# main.net
KiCad netlist of a schematic drawn in Altium Designer
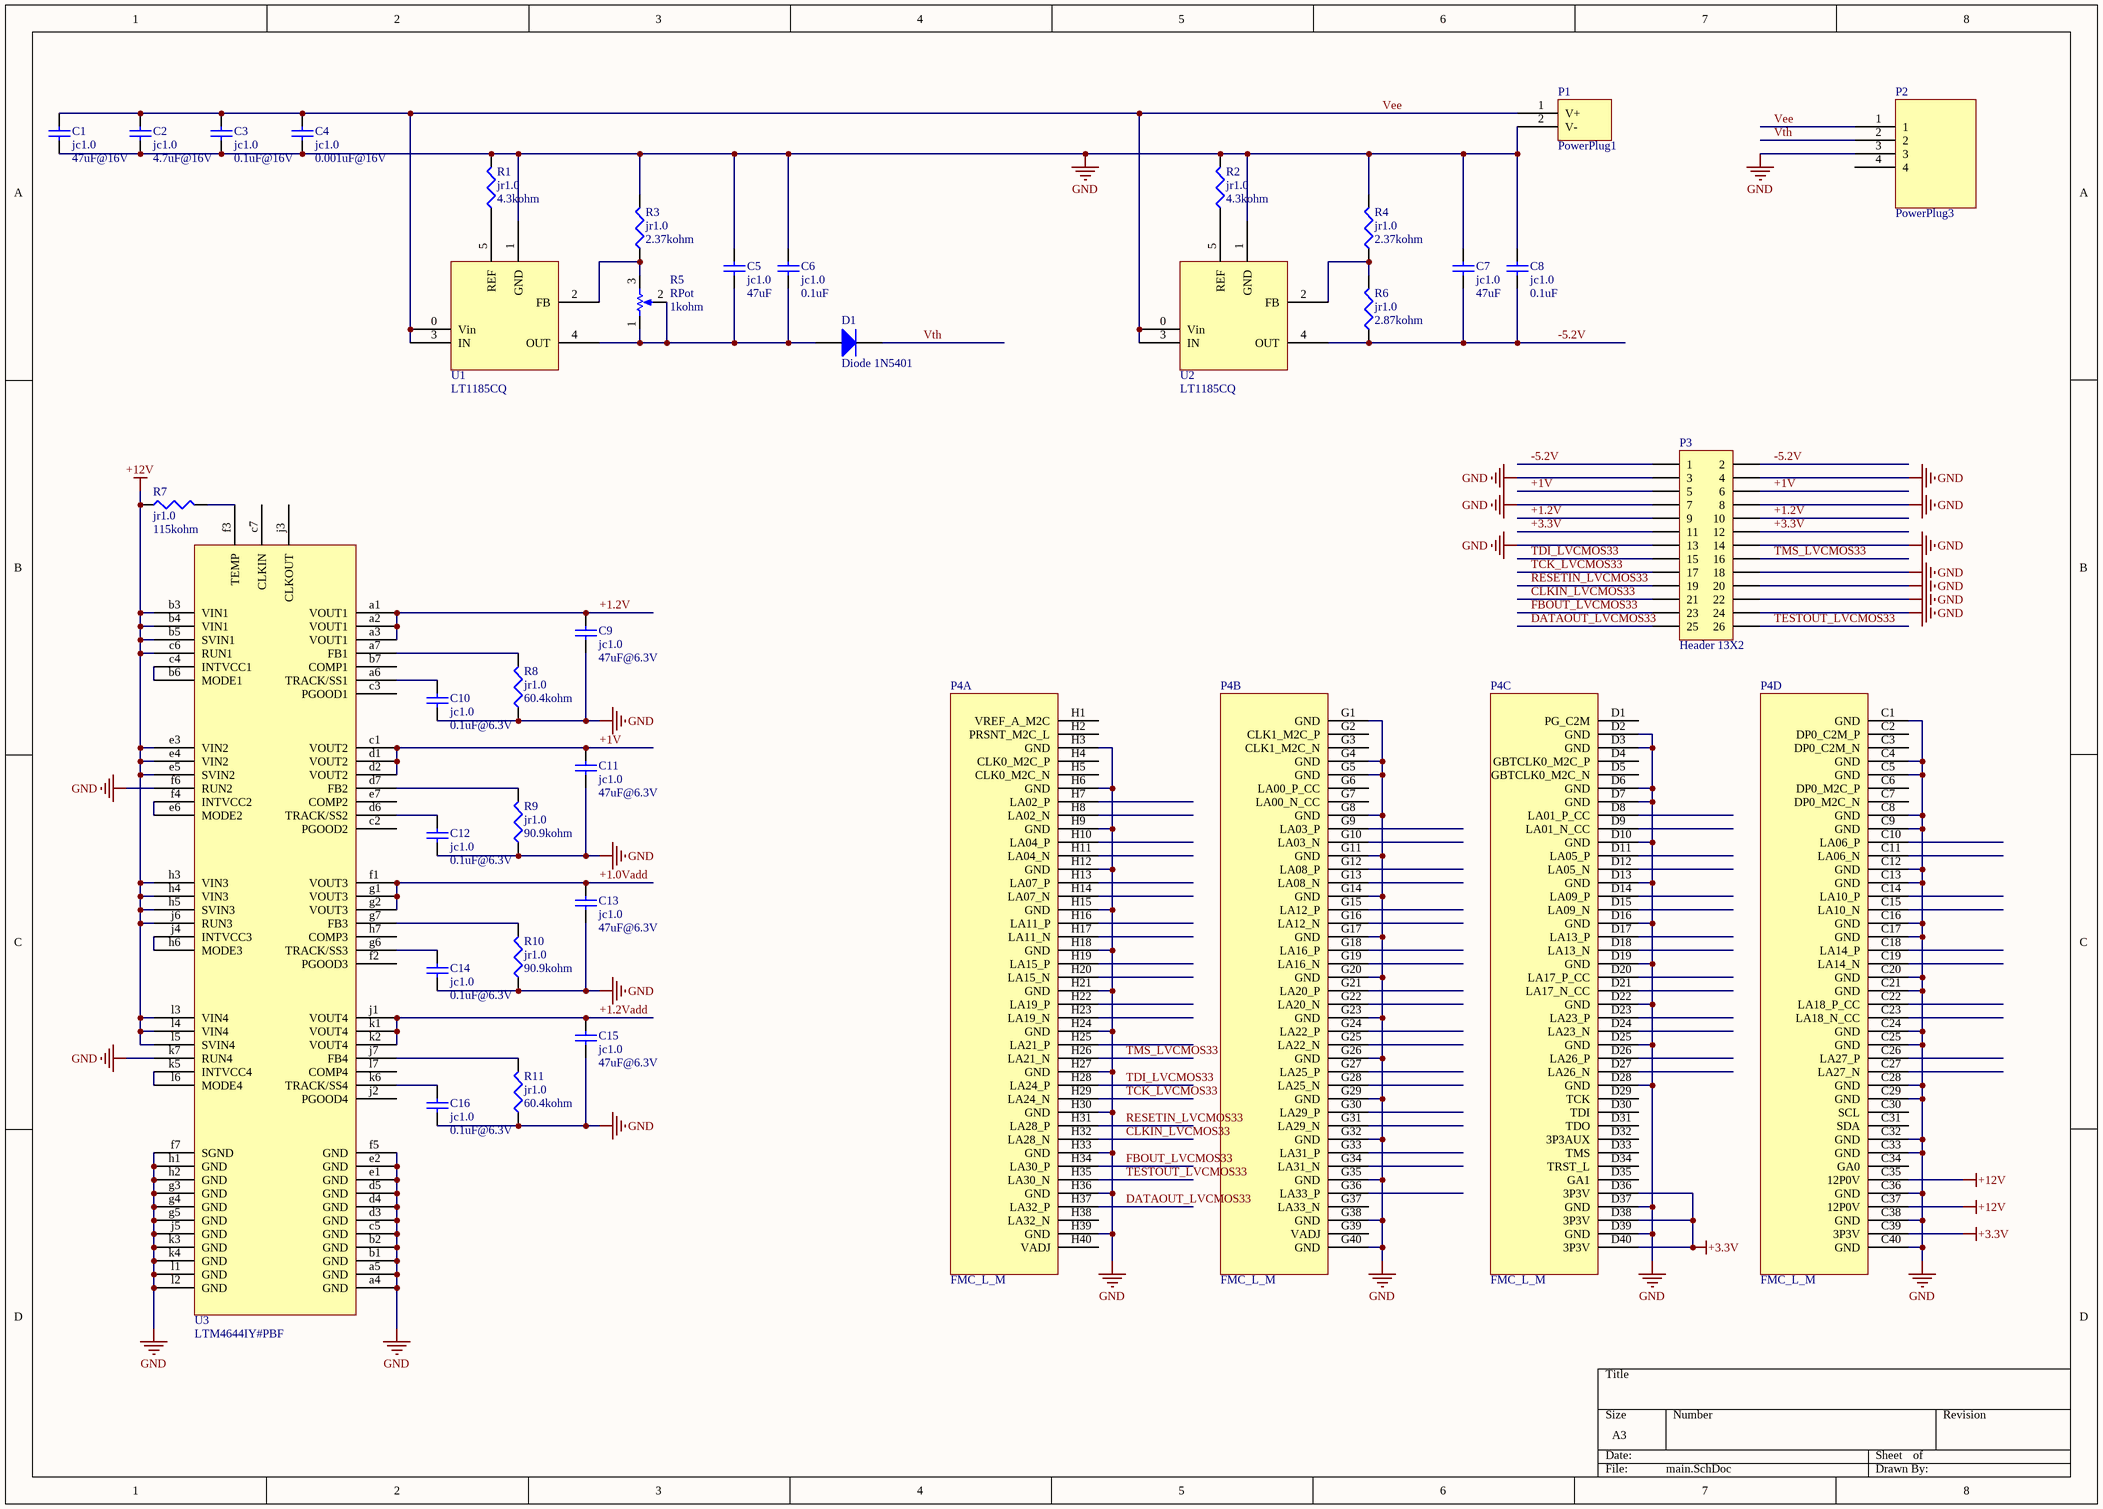
[diagram p0: main.SchDoc]

(export (version "E")
  (design (tool "Eeschema 10.0.6"))
  (components
    (comp (ref "C1")
      (value "jc1.0")
      (footprint "2220")
      (description "Capacitor")
      (fields (field (name "ALTIUM_VALUE") "47uF@16V") (field (name "PUBLISHER") "Altium Limited"))
      (libsource (lib "LIB01DXP2006SchLib") (part "Cap"))
    )
    (comp (ref "C2")
      (value "jc1.0")
      (footprint "2220")
      (description "Capacitor")
      (fields (field (name "ALTIUM_VALUE") "4.7uF@16V") (field (name "PUBLISHER") "Altium Limited"))
      (libsource (lib "LIB01DXP2006SchLib") (part "Cap"))
    )
    (comp (ref "C3")
      (value "jc1.0")
      (footprint "2220")
      (description "Capacitor")
      (fields (field (name "ALTIUM_VALUE") "0.1uF@16V") (field (name "PUBLISHER") "Altium Limited"))
      (libsource (lib "LIB01DXP2006SchLib") (part "Cap"))
    )
    (comp (ref "C4")
      (value "jc1.0")
      (footprint "2220")
      (description "Capacitor")
      (fields (field (name "ALTIUM_VALUE") "0.001uF@16V") (field (name "PUBLISHER") "Altium Limited"))
      (libsource (lib "LIB01DXP2006SchLib") (part "Cap"))
    )
    (comp (ref "C5")
      (value "jc1.0")
      (footprint "2220")
      (description "Capacitor")
      (fields (field (name "ALTIUM_VALUE") "47uF") (field (name "PUBLISHER") "Altium Limited"))
      (libsource (lib "LIB01DXP2006SchLib") (part "Cap"))
    )
    (comp (ref "C6")
      (value "jc1.0")
      (footprint "2220")
      (description "Capacitor")
      (fields (field (name "ALTIUM_VALUE") "0.1uF") (field (name "PUBLISHER") "Altium Limited"))
      (libsource (lib "LIB01DXP2006SchLib") (part "Cap"))
    )
    (comp (ref "C7")
      (value "jc1.0")
      (footprint "2220")
      (description "Capacitor")
      (fields (field (name "ALTIUM_VALUE") "47uF") (field (name "PUBLISHER") "Altium Limited"))
      (libsource (lib "LIB01DXP2006SchLib") (part "Cap"))
    )
    (comp (ref "C8")
      (value "jc1.0")
      (footprint "2220")
      (description "Capacitor")
      (fields (field (name "ALTIUM_VALUE") "0.1uF") (field (name "PUBLISHER") "Altium Limited"))
      (libsource (lib "LIB01DXP2006SchLib") (part "Cap"))
    )
    (comp (ref "C9")
      (value "jc1.0")
      (footprint "0805")
      (description "Capacitor")
      (fields (field (name "ALTIUM_VALUE") "47uF@6.3V") (field (name "PUBLISHER") "Altium Limited"))
      (libsource (lib "LIB01DXP2006SchLib") (part "Cap"))
    )
    (comp (ref "C10")
      (value "jc1.0")
      (footprint "0402")
      (description "Capacitor")
      (fields (field (name "ALTIUM_VALUE") "0.1uF@6.3V") (field (name "PUBLISHER") "Altium Limited"))
      (libsource (lib "LIB01DXP2006SchLib") (part "Cap"))
    )
    (comp (ref "C11")
      (value "jc1.0")
      (footprint "0805")
      (description "Capacitor")
      (fields (field (name "ALTIUM_VALUE") "47uF@6.3V") (field (name "PUBLISHER") "Altium Limited"))
      (libsource (lib "LIB01DXP2006SchLib") (part "Cap"))
    )
    (comp (ref "C12")
      (value "jc1.0")
      (footprint "0402")
      (description "Capacitor")
      (fields (field (name "ALTIUM_VALUE") "0.1uF@6.3V") (field (name "PUBLISHER") "Altium Limited"))
      (libsource (lib "LIB01DXP2006SchLib") (part "Cap"))
    )
    (comp (ref "C13")
      (value "jc1.0")
      (footprint "0805")
      (description "Capacitor")
      (fields (field (name "ALTIUM_VALUE") "47uF@6.3V") (field (name "PUBLISHER") "Altium Limited"))
      (libsource (lib "LIB01DXP2006SchLib") (part "Cap"))
    )
    (comp (ref "C14")
      (value "jc1.0")
      (footprint "0402")
      (description "Capacitor")
      (fields (field (name "ALTIUM_VALUE") "0.1uF@6.3V") (field (name "PUBLISHER") "Altium Limited"))
      (libsource (lib "LIB01DXP2006SchLib") (part "Cap"))
    )
    (comp (ref "C15")
      (value "jc1.0")
      (footprint "0805")
      (description "Capacitor")
      (fields (field (name "ALTIUM_VALUE") "47uF@6.3V") (field (name "PUBLISHER") "Altium Limited"))
      (libsource (lib "LIB01DXP2006SchLib") (part "Cap"))
    )
    (comp (ref "C16")
      (value "jc1.0")
      (footprint "0402")
      (description "Capacitor")
      (fields (field (name "ALTIUM_VALUE") "0.1uF@6.3V") (field (name "PUBLISHER") "Altium Limited"))
      (libsource (lib "LIB01DXP2006SchLib") (part "Cap"))
    )
    (comp (ref "D1")
      (value "Diode 1N5401")
      (footprint "DO-201AD")
      (description "3 Amp General Purpose Rectifier")
      (fields (field (name "PUBLISHER") "Altium Limited"))
      (libsource (lib "Miscellaneous Devices") (part "Diode 1N5401"))
    )
    (comp (ref "P1")
      (value "PowerPlug1")
      (footprint "POWERPLUG1")
      (libsource (lib "LIB01DXP2006SchLib") (part "PowerPlug1"))
    )
    (comp (ref "P2")
      (value "PowerPlug3")
      (footprint "POWERPLUG3")
      (libsource (lib "LIB01DXP2006SchLib") (part "PowerPlug3"))
    )
    (comp (ref "P3")
      (value "Header 13X2")
      (footprint "HDR2X13")
      (description "Header, 13-Pin, Dual row")
      (fields (field (name "PUBLISHER") "Altium Limited"))
      (libsource (lib "Miscellaneous Connectors") (part "Header 13X2"))
    )
    (comp (ref "P4")
      (value "FMC_L_M")
      (footprint "ASP-134606-01")
      (libsource (lib "LIB01DXP2006SchLib") (part "FMC_L_M"))
    )
    (comp (ref "R1")
      (value "jr1.0")
      (footprint "0805")
      (description "Resistor")
      (fields (field (name "ALTIUM_VALUE") "4.3kohm") (field (name "PUBLISHER") "Altium Limited"))
      (libsource (lib "LIB01DXP2006SchLib") (part "Res"))
    )
    (comp (ref "R2")
      (value "jr1.0")
      (footprint "0805")
      (description "Resistor")
      (fields (field (name "ALTIUM_VALUE") "4.3kohm") (field (name "PUBLISHER") "Altium Limited"))
      (libsource (lib "LIB01DXP2006SchLib") (part "Res"))
    )
    (comp (ref "R3")
      (value "jr1.0")
      (footprint "0805")
      (description "Resistor")
      (fields (field (name "ALTIUM_VALUE") "2.37kohm") (field (name "PUBLISHER") "Altium Limited"))
      (libsource (lib "LIB01DXP2006SchLib") (part "Res"))
    )
    (comp (ref "R4")
      (value "jr1.0")
      (footprint "0805")
      (description "Resistor")
      (fields (field (name "ALTIUM_VALUE") "2.37kohm") (field (name "PUBLISHER") "Altium Limited"))
      (libsource (lib "LIB01DXP2006SchLib") (part "Res"))
    )
    (comp (ref "R5")
      (value "RPot")
      (footprint "VR5")
      (description "Potentiometer")
      (fields (field (name "ALTIUM_VALUE") "1kohm") (field (name "PUBLISHER") "Altium Limited"))
      (libsource (lib "LIB01DXP2006SchLib") (part "RPot"))
    )
    (comp (ref "R6")
      (value "jr1.0")
      (footprint "0805")
      (description "Resistor")
      (fields (field (name "ALTIUM_VALUE") "2.87kohm") (field (name "PUBLISHER") "Altium Limited"))
      (libsource (lib "LIB01DXP2006SchLib") (part "Res"))
    )
    (comp (ref "R7")
      (value "jr1.0")
      (footprint "0402")
      (description "Resistor")
      (fields (field (name "ALTIUM_VALUE") "115kohm") (field (name "PUBLISHER") "Altium Limited"))
      (libsource (lib "LIB01DXP2006SchLib") (part "Res"))
    )
    (comp (ref "R8")
      (value "jr1.0")
      (footprint "0805")
      (description "Resistor")
      (fields (field (name "ALTIUM_VALUE") "60.4kohm") (field (name "PUBLISHER") "Altium Limited"))
      (libsource (lib "LIB01DXP2006SchLib") (part "Res"))
    )
    (comp (ref "R9")
      (value "jr1.0")
      (footprint "0805")
      (description "Resistor")
      (fields (field (name "ALTIUM_VALUE") "90.9kohm") (field (name "PUBLISHER") "Altium Limited"))
      (libsource (lib "LIB01DXP2006SchLib") (part "Res"))
    )
    (comp (ref "R10")
      (value "jr1.0")
      (footprint "0805")
      (description "Resistor")
      (fields (field (name "ALTIUM_VALUE") "90.9kohm") (field (name "PUBLISHER") "Altium Limited"))
      (libsource (lib "LIB01DXP2006SchLib") (part "Res"))
    )
    (comp (ref "R11")
      (value "jr1.0")
      (footprint "0805")
      (description "Resistor")
      (fields (field (name "ALTIUM_VALUE") "60.4kohm") (field (name "PUBLISHER") "Altium Limited"))
      (libsource (lib "LIB01DXP2006SchLib") (part "Res"))
    )
    (comp (ref "U1")
      (value "LT1185CQ")
      (footprint "LP5 - 1185")
      (libsource (lib "LIB01DXP2006SchLib") (part "LT1185CQ"))
    )
    (comp (ref "U2")
      (value "LT1185CQ")
      (footprint "LP5 - 1185")
      (libsource (lib "LIB01DXP2006SchLib") (part "LT1185CQ"))
    )
    (comp (ref "U3")
      (value "LTM4644IY#PBF")
      (footprint "BGA77C127P7X11_900X1500X521")
      (libsource (lib "LIB01DXP2006SchLib") (part "LTM4644IY#PBF"))
    )
  )
  (nets
    (net (code "1") (name "+3.3V") (class "Default")
      (node (ref "P3") (pin "11") (pinfunction "11_11") (pintype "passive"))
      (node (ref "P3") (pin "12") (pinfunction "12_12") (pintype "passive"))
      (node (ref "P4") (pin "C39") (pinfunction "3P3V_C39") (pintype "passive"))
      (node (ref "P4") (pin "D36") (pinfunction "3P3V_D36") (pintype "passive"))
      (node (ref "P4") (pin "D38") (pinfunction "3P3V_D38") (pintype "passive"))
      (node (ref "P4") (pin "D40") (pinfunction "3P3V_D40") (pintype "passive"))
    )
    (net (code "2") (name "+12V") (class "Default")
      (node (ref "P4") (pin "C35") (pinfunction "12P0V_C35") (pintype "passive"))
      (node (ref "P4") (pin "C37") (pinfunction "12P0V_C37") (pintype "passive"))
      (node (ref "R7") (pin "1") (pinfunction "1_1") (pintype "passive"))
      (node (ref "U3") (pin "b3") (pinfunction "VIN1_b3") (pintype "passive"))
      (node (ref "U3") (pin "b4") (pinfunction "VIN1_b4") (pintype "passive"))
      (node (ref "U3") (pin "b5") (pinfunction "SVIN1_b5") (pintype "passive"))
      (node (ref "U3") (pin "c6") (pinfunction "RUN1_c6") (pintype "passive"))
      (node (ref "U3") (pin "e3") (pinfunction "VIN2_e3") (pintype "passive"))
      (node (ref "U3") (pin "e4") (pinfunction "VIN2_e4") (pintype "passive"))
      (node (ref "U3") (pin "e5") (pinfunction "SVIN2_e5") (pintype "passive"))
      (node (ref "U3") (pin "h3") (pinfunction "VIN3_h3") (pintype "passive"))
      (node (ref "U3") (pin "h4") (pinfunction "VIN3_h4") (pintype "passive"))
      (node (ref "U3") (pin "h5") (pinfunction "SVIN3_h5") (pintype "passive"))
      (node (ref "U3") (pin "j6") (pinfunction "RUN3_j6") (pintype "passive"))
      (node (ref "U3") (pin "l3") (pinfunction "VIN4_l3") (pintype "passive"))
      (node (ref "U3") (pin "l4") (pinfunction "VIN4_l4") (pintype "passive"))
      (node (ref "U3") (pin "l5") (pinfunction "SVIN4_l5") (pintype "passive"))
    )
    (net (code "3") (name "/+1.0Vadd") (class "Default")
      (node (ref "C13") (pin "2") (pinfunction "2_2") (pintype "passive"))
      (node (ref "U3") (pin "f1") (pinfunction "VOUT3_f1") (pintype "passive"))
      (node (ref "U3") (pin "g1") (pinfunction "VOUT3_g1") (pintype "passive"))
      (node (ref "U3") (pin "g2") (pinfunction "VOUT3_g2") (pintype "passive"))
    )
    (net (code "4") (name "/+1.2V") (class "Default")
      (node (ref "C9") (pin "2") (pinfunction "2_2") (pintype "passive"))
      (node (ref "P3") (pin "10") (pinfunction "10_10") (pintype "passive"))
      (node (ref "P3") (pin "9") (pinfunction "9_9") (pintype "passive"))
      (node (ref "U3") (pin "a1") (pinfunction "VOUT1_a1") (pintype "passive"))
      (node (ref "U3") (pin "a2") (pinfunction "VOUT1_a2") (pintype "passive"))
      (node (ref "U3") (pin "a3") (pinfunction "VOUT1_a3") (pintype "passive"))
    )
    (net (code "5") (name "/+1.2Vadd") (class "Default")
      (node (ref "C15") (pin "2") (pinfunction "2_2") (pintype "passive"))
      (node (ref "U3") (pin "j1") (pinfunction "VOUT4_j1") (pintype "passive"))
      (node (ref "U3") (pin "k1") (pinfunction "VOUT4_k1") (pintype "passive"))
      (node (ref "U3") (pin "k2") (pinfunction "VOUT4_k2") (pintype "passive"))
    )
    (net (code "6") (name "/+1V") (class "Default")
      (node (ref "C11") (pin "2") (pinfunction "2_2") (pintype "passive"))
      (node (ref "P3") (pin "5") (pinfunction "5_5") (pintype "passive"))
      (node (ref "P3") (pin "6") (pinfunction "6_6") (pintype "passive"))
      (node (ref "U3") (pin "c1") (pinfunction "VOUT2_c1") (pintype "passive"))
      (node (ref "U3") (pin "d1") (pinfunction "VOUT2_d1") (pintype "passive"))
      (node (ref "U3") (pin "d2") (pinfunction "VOUT2_d2") (pintype "passive"))
    )
    (net (code "7") (name "/-5.2V") (class "Default")
      (node (ref "C7") (pin "1") (pinfunction "1_1") (pintype "passive"))
      (node (ref "C8") (pin "1") (pinfunction "1_1") (pintype "passive"))
      (node (ref "P3") (pin "1") (pinfunction "1_1") (pintype "passive"))
      (node (ref "P3") (pin "2") (pinfunction "2_2") (pintype "passive"))
      (node (ref "R6") (pin "1") (pinfunction "1_1") (pintype "passive"))
      (node (ref "U2") (pin "4") (pinfunction "OUT_4") (pintype "passive"))
    )
    (net (code "8") (name "/CLKIN_LVCMOS33") (class "Default")
      (node (ref "P3") (pin "21") (pinfunction "21_21") (pintype "passive"))
      (node (ref "P4") (pin "H32") (pinfunction "LA28_N_H32") (pintype "passive"))
    )
    (net (code "9") (name "/DATAOUT_LVCMOS33") (class "Default")
      (node (ref "P3") (pin "25") (pinfunction "25_25") (pintype "passive"))
      (node (ref "P4") (pin "H37") (pinfunction "LA32_P_H37") (pintype "passive"))
    )
    (net (code "10") (name "/FBOUT_LVCMOS33") (class "Default")
      (node (ref "P3") (pin "23") (pinfunction "23_23") (pintype "passive"))
      (node (ref "P4") (pin "H34") (pinfunction "LA30_P_H34") (pintype "passive"))
    )
    (net (code "11") (name "/RESETIN_LVCMOS33") (class "Default")
      (node (ref "P3") (pin "19") (pinfunction "19_19") (pintype "passive"))
      (node (ref "P4") (pin "H31") (pinfunction "LA28_P_H31") (pintype "passive"))
    )
    (net (code "12") (name "/TCK_LVCMOS33") (class "Default")
      (node (ref "P3") (pin "17") (pinfunction "17_17") (pintype "passive"))
      (node (ref "P4") (pin "H29") (pinfunction "LA24_N_H29") (pintype "passive"))
    )
    (net (code "13") (name "/TDI_LVCMOS33") (class "Default")
      (node (ref "P3") (pin "15") (pinfunction "15_15") (pintype "passive"))
      (node (ref "P4") (pin "H28") (pinfunction "LA24_P_H28") (pintype "passive"))
    )
    (net (code "14") (name "/TESTOUT_LVCMOS33") (class "Default")
      (node (ref "P3") (pin "26") (pinfunction "26_26") (pintype "passive"))
      (node (ref "P4") (pin "H35") (pinfunction "LA30_N_H35") (pintype "passive"))
    )
    (net (code "15") (name "/TMS_LVCMOS33") (class "Default")
      (node (ref "P3") (pin "16") (pinfunction "16_16") (pintype "passive"))
      (node (ref "P4") (pin "H26") (pinfunction "LA21_N_H26") (pintype "passive"))
    )
    (net (code "16") (name "/Vee") (class "Default")
      (node (ref "C1") (pin "2") (pinfunction "2_2") (pintype "passive"))
      (node (ref "C2") (pin "2") (pinfunction "2_2") (pintype "passive"))
      (node (ref "C3") (pin "2") (pinfunction "2_2") (pintype "passive"))
      (node (ref "C4") (pin "2") (pinfunction "2_2") (pintype "passive"))
      (node (ref "P1") (pin "1") (pinfunction "V+_1") (pintype "passive"))
      (node (ref "P2") (pin "1") (pinfunction "1_1") (pintype "passive"))
      (node (ref "U1") (pin "0") (pinfunction "Vin_0") (pintype "passive"))
      (node (ref "U1") (pin "3") (pinfunction "IN_3") (pintype "passive"))
      (node (ref "U2") (pin "0") (pinfunction "Vin_0") (pintype "passive"))
      (node (ref "U2") (pin "3") (pinfunction "IN_3") (pintype "passive"))
    )
    (net (code "17") (name "/Vth") (class "Default")
      (node (ref "D1") (pin "2") (pinfunction "K_2") (pintype "passive"))
      (node (ref "P2") (pin "2") (pinfunction "2_2") (pintype "passive"))
    )
    (net (code "18") (name "GND") (class "Default")
      (node (ref "C1") (pin "1") (pinfunction "1_1") (pintype "passive"))
      (node (ref "C10") (pin "1") (pinfunction "1_1") (pintype "passive"))
      (node (ref "C11") (pin "1") (pinfunction "1_1") (pintype "passive"))
      (node (ref "C12") (pin "1") (pinfunction "1_1") (pintype "passive"))
      (node (ref "C13") (pin "1") (pinfunction "1_1") (pintype "passive"))
      (node (ref "C14") (pin "1") (pinfunction "1_1") (pintype "passive"))
      (node (ref "C15") (pin "1") (pinfunction "1_1") (pintype "passive"))
      (node (ref "C16") (pin "1") (pinfunction "1_1") (pintype "passive"))
      (node (ref "C2") (pin "1") (pinfunction "1_1") (pintype "passive"))
      (node (ref "C3") (pin "1") (pinfunction "1_1") (pintype "passive"))
      (node (ref "C4") (pin "1") (pinfunction "1_1") (pintype "passive"))
      (node (ref "C5") (pin "2") (pinfunction "2_2") (pintype "passive"))
      (node (ref "C6") (pin "2") (pinfunction "2_2") (pintype "passive"))
      (node (ref "C7") (pin "2") (pinfunction "2_2") (pintype "passive"))
      (node (ref "C8") (pin "2") (pinfunction "2_2") (pintype "passive"))
      (node (ref "C9") (pin "1") (pinfunction "1_1") (pintype "passive"))
      (node (ref "P1") (pin "2") (pinfunction "V-_2") (pintype "passive"))
      (node (ref "P2") (pin "3") (pinfunction "3_3") (pintype "passive"))
      (node (ref "P3") (pin "13") (pinfunction "13_13") (pintype "passive"))
      (node (ref "P3") (pin "14") (pinfunction "14_14") (pintype "passive"))
      (node (ref "P3") (pin "18") (pinfunction "18_18") (pintype "passive"))
      (node (ref "P3") (pin "20") (pinfunction "20_20") (pintype "passive"))
      (node (ref "P3") (pin "22") (pinfunction "22_22") (pintype "passive"))
      (node (ref "P3") (pin "24") (pinfunction "24_24") (pintype "passive"))
      (node (ref "P3") (pin "3") (pinfunction "3_3") (pintype "passive"))
      (node (ref "P3") (pin "4") (pinfunction "4_4") (pintype "passive"))
      (node (ref "P3") (pin "7") (pinfunction "7_7") (pintype "passive"))
      (node (ref "P3") (pin "8") (pinfunction "8_8") (pintype "passive"))
      (node (ref "P4") (pin "C1") (pinfunction "GND_C1") (pintype "passive"))
      (node (ref "P4") (pin "C12") (pinfunction "GND_C12") (pintype "passive"))
      (node (ref "P4") (pin "C13") (pinfunction "GND_C13") (pintype "passive"))
      (node (ref "P4") (pin "C16") (pinfunction "GND_C16") (pintype "passive"))
      (node (ref "P4") (pin "C17") (pinfunction "GND_C17") (pintype "passive"))
      (node (ref "P4") (pin "C20") (pinfunction "GND_C20") (pintype "passive"))
      (node (ref "P4") (pin "C21") (pinfunction "GND_C21") (pintype "passive"))
      (node (ref "P4") (pin "C24") (pinfunction "GND_C24") (pintype "passive"))
      (node (ref "P4") (pin "C25") (pinfunction "GND_C25") (pintype "passive"))
      (node (ref "P4") (pin "C28") (pinfunction "GND_C28") (pintype "passive"))
      (node (ref "P4") (pin "C29") (pinfunction "GND_C29") (pintype "passive"))
      (node (ref "P4") (pin "C32") (pinfunction "GND_C32") (pintype "passive"))
      (node (ref "P4") (pin "C33") (pinfunction "GND_C33") (pintype "passive"))
      (node (ref "P4") (pin "C36") (pinfunction "GND_C36") (pintype "passive"))
      (node (ref "P4") (pin "C38") (pinfunction "GND_C38") (pintype "passive"))
      (node (ref "P4") (pin "C4") (pinfunction "GND_C4") (pintype "passive"))
      (node (ref "P4") (pin "C40") (pinfunction "GND_C40") (pintype "passive"))
      (node (ref "P4") (pin "C5") (pinfunction "GND_C5") (pintype "passive"))
      (node (ref "P4") (pin "C8") (pinfunction "GND_C8") (pintype "passive"))
      (node (ref "P4") (pin "C9") (pinfunction "GND_C9") (pintype "passive"))
      (node (ref "P4") (pin "D10") (pinfunction "GND_D10") (pintype "passive"))
      (node (ref "P4") (pin "D13") (pinfunction "GND_D13") (pintype "passive"))
      (node (ref "P4") (pin "D16") (pinfunction "GND_D16") (pintype "passive"))
      (node (ref "P4") (pin "D19") (pinfunction "GND_D19") (pintype "passive"))
      (node (ref "P4") (pin "D2") (pinfunction "GND_D2") (pintype "passive"))
      (node (ref "P4") (pin "D22") (pinfunction "GND_D22") (pintype "passive"))
      (node (ref "P4") (pin "D25") (pinfunction "GND_D25") (pintype "passive"))
      (node (ref "P4") (pin "D28") (pinfunction "GND_D28") (pintype "passive"))
      (node (ref "P4") (pin "D3") (pinfunction "GND_D3") (pintype "passive"))
      (node (ref "P4") (pin "D37") (pinfunction "GND_D37") (pintype "passive"))
      (node (ref "P4") (pin "D39") (pinfunction "GND_D39") (pintype "passive"))
      (node (ref "P4") (pin "D6") (pinfunction "GND_D6") (pintype "passive"))
      (node (ref "P4") (pin "D7") (pinfunction "GND_D7") (pintype "passive"))
      (node (ref "P4") (pin "G1") (pinfunction "GND_G1") (pintype "passive"))
      (node (ref "P4") (pin "G11") (pinfunction "GND_G11") (pintype "passive"))
      (node (ref "P4") (pin "G14") (pinfunction "GND_G14") (pintype "passive"))
      (node (ref "P4") (pin "G17") (pinfunction "GND_G17") (pintype "passive"))
      (node (ref "P4") (pin "G20") (pinfunction "GND_G20") (pintype "passive"))
      (node (ref "P4") (pin "G23") (pinfunction "GND_G23") (pintype "passive"))
      (node (ref "P4") (pin "G26") (pinfunction "GND_G26") (pintype "passive"))
      (node (ref "P4") (pin "G29") (pinfunction "GND_G29") (pintype "passive"))
      (node (ref "P4") (pin "G32") (pinfunction "GND_G32") (pintype "passive"))
      (node (ref "P4") (pin "G35") (pinfunction "GND_G35") (pintype "passive"))
      (node (ref "P4") (pin "G38") (pinfunction "GND_G38") (pintype "passive"))
      (node (ref "P4") (pin "G4") (pinfunction "GND_G4") (pintype "passive"))
      (node (ref "P4") (pin "G40") (pinfunction "GND_G40") (pintype "passive"))
      (node (ref "P4") (pin "G5") (pinfunction "GND_G5") (pintype "passive"))
      (node (ref "P4") (pin "G8") (pinfunction "GND_G8") (pintype "passive"))
      (node (ref "P4") (pin "H12") (pinfunction "GND_H12") (pintype "passive"))
      (node (ref "P4") (pin "H15") (pinfunction "GND_H15") (pintype "passive"))
      (node (ref "P4") (pin "H18") (pinfunction "GND_H18") (pintype "passive"))
      (node (ref "P4") (pin "H21") (pinfunction "GND_H21") (pintype "passive"))
      (node (ref "P4") (pin "H24") (pinfunction "GND_H24") (pintype "passive"))
      (node (ref "P4") (pin "H27") (pinfunction "GND_H27") (pintype "passive"))
      (node (ref "P4") (pin "H3") (pinfunction "GND_H3") (pintype "passive"))
      (node (ref "P4") (pin "H30") (pinfunction "GND_H30") (pintype "passive"))
      (node (ref "P4") (pin "H33") (pinfunction "GND_H33") (pintype "passive"))
      (node (ref "P4") (pin "H36") (pinfunction "GND_H36") (pintype "passive"))
      (node (ref "P4") (pin "H39") (pinfunction "GND_H39") (pintype "passive"))
      (node (ref "P4") (pin "H6") (pinfunction "GND_H6") (pintype "passive"))
      (node (ref "P4") (pin "H9") (pinfunction "GND_H9") (pintype "passive"))
      (node (ref "R1") (pin "2") (pinfunction "2_2") (pintype "passive"))
      (node (ref "R10") (pin "1") (pinfunction "1_1") (pintype "passive"))
      (node (ref "R11") (pin "1") (pinfunction "1_1") (pintype "passive"))
      (node (ref "R2") (pin "2") (pinfunction "2_2") (pintype "passive"))
      (node (ref "R3") (pin "2") (pinfunction "2_2") (pintype "passive"))
      (node (ref "R4") (pin "2") (pinfunction "2_2") (pintype "passive"))
      (node (ref "R8") (pin "1") (pinfunction "1_1") (pintype "passive"))
      (node (ref "R9") (pin "1") (pinfunction "1_1") (pintype "passive"))
      (node (ref "U1") (pin "1") (pinfunction "GND_1") (pintype "passive"))
      (node (ref "U2") (pin "1") (pinfunction "GND_1") (pintype "passive"))
      (node (ref "U3") (pin "a4") (pinfunction "GND_a4") (pintype "passive"))
      (node (ref "U3") (pin "a5") (pinfunction "GND_a5") (pintype "passive"))
      (node (ref "U3") (pin "b1") (pinfunction "GND_b1") (pintype "passive"))
      (node (ref "U3") (pin "b2") (pinfunction "GND_b2") (pintype "passive"))
      (node (ref "U3") (pin "c5") (pinfunction "GND_c5") (pintype "passive"))
      (node (ref "U3") (pin "d3") (pinfunction "GND_d3") (pintype "passive"))
      (node (ref "U3") (pin "d4") (pinfunction "GND_d4") (pintype "passive"))
      (node (ref "U3") (pin "d5") (pinfunction "GND_d5") (pintype "passive"))
      (node (ref "U3") (pin "e1") (pinfunction "GND_e1") (pintype "passive"))
      (node (ref "U3") (pin "e2") (pinfunction "GND_e2") (pintype "passive"))
      (node (ref "U3") (pin "f5") (pinfunction "GND_f5") (pintype "passive"))
      (node (ref "U3") (pin "f6") (pinfunction "RUN2_f6") (pintype "passive"))
      (node (ref "U3") (pin "f7") (pinfunction "SGND_f7") (pintype "passive"))
      (node (ref "U3") (pin "g3") (pinfunction "GND_g3") (pintype "passive"))
      (node (ref "U3") (pin "g4") (pinfunction "GND_g4") (pintype "passive"))
      (node (ref "U3") (pin "g5") (pinfunction "GND_g5") (pintype "passive"))
      (node (ref "U3") (pin "h1") (pinfunction "GND_h1") (pintype "passive"))
      (node (ref "U3") (pin "h2") (pinfunction "GND_h2") (pintype "passive"))
      (node (ref "U3") (pin "j5") (pinfunction "GND_j5") (pintype "passive"))
      (node (ref "U3") (pin "k3") (pinfunction "GND_k3") (pintype "passive"))
      (node (ref "U3") (pin "k4") (pinfunction "GND_k4") (pintype "passive"))
      (node (ref "U3") (pin "k7") (pinfunction "RUN4_k7") (pintype "passive"))
      (node (ref "U3") (pin "l1") (pinfunction "GND_l1") (pintype "passive"))
      (node (ref "U3") (pin "l2") (pinfunction "GND_l2") (pintype "passive"))
    )
    (net (code "19") (name "Net-(D1-A)") (class "Default")
      (node (ref "C5") (pin "1") (pinfunction "1_1") (pintype "passive"))
      (node (ref "C6") (pin "1") (pinfunction "1_1") (pintype "passive"))
      (node (ref "D1") (pin "1") (pinfunction "A_1") (pintype "passive"))
      (node (ref "R5") (pin "1") (pinfunction "TOP_1") (pintype "passive"))
      (node (ref "R5") (pin "2") (pinfunction "TAP_2") (pintype "passive"))
      (node (ref "U1") (pin "4") (pinfunction "OUT_4") (pintype "passive"))
    )
    (net (code "20") (name "Net-(R5-BOT)") (class "Default")
      (node (ref "R3") (pin "1") (pinfunction "1_1") (pintype "passive"))
      (node (ref "R5") (pin "3") (pinfunction "BOT_3") (pintype "passive"))
      (node (ref "U1") (pin "2") (pinfunction "FB_2") (pintype "passive"))
    )
    (net (code "21") (name "Net-(U1-REF)") (class "Default")
      (node (ref "R1") (pin "1") (pinfunction "1_1") (pintype "passive"))
      (node (ref "U1") (pin "5") (pinfunction "REF_5") (pintype "passive"))
    )
    (net (code "22") (name "Net-(U2-FB)") (class "Default")
      (node (ref "R4") (pin "1") (pinfunction "1_1") (pintype "passive"))
      (node (ref "R6") (pin "2") (pinfunction "2_2") (pintype "passive"))
      (node (ref "U2") (pin "2") (pinfunction "FB_2") (pintype "passive"))
    )
    (net (code "23") (name "Net-(U2-REF)") (class "Default")
      (node (ref "R2") (pin "1") (pinfunction "1_1") (pintype "passive"))
      (node (ref "U2") (pin "5") (pinfunction "REF_5") (pintype "passive"))
    )
    (net (code "24") (name "Net-(U3-FB1)") (class "Default")
      (node (ref "R8") (pin "2") (pinfunction "2_2") (pintype "passive"))
      (node (ref "U3") (pin "a7") (pinfunction "FB1_a7") (pintype "passive"))
    )
    (net (code "25") (name "Net-(U3-FB2)") (class "Default")
      (node (ref "R9") (pin "2") (pinfunction "2_2") (pintype "passive"))
      (node (ref "U3") (pin "d7") (pinfunction "FB2_d7") (pintype "passive"))
    )
    (net (code "26") (name "Net-(U3-FB3)") (class "Default")
      (node (ref "R10") (pin "2") (pinfunction "2_2") (pintype "passive"))
      (node (ref "U3") (pin "g7") (pinfunction "FB3_g7") (pintype "passive"))
    )
    (net (code "27") (name "Net-(U3-FB4)") (class "Default")
      (node (ref "R11") (pin "2") (pinfunction "2_2") (pintype "passive"))
      (node (ref "U3") (pin "j7") (pinfunction "FB4_j7") (pintype "passive"))
    )
    (net (code "28") (name "Net-(U3-INTVCC1)") (class "Default")
      (node (ref "U3") (pin "b6") (pinfunction "MODE1_b6") (pintype "passive"))
      (node (ref "U3") (pin "c4") (pinfunction "INTVCC1_c4") (pintype "passive"))
    )
    (net (code "29") (name "Net-(U3-INTVCC2)") (class "Default")
      (node (ref "U3") (pin "e6") (pinfunction "MODE2_e6") (pintype "passive"))
      (node (ref "U3") (pin "f4") (pinfunction "INTVCC2_f4") (pintype "passive"))
    )
    (net (code "30") (name "Net-(U3-INTVCC3)") (class "Default")
      (node (ref "U3") (pin "h6") (pinfunction "MODE3_h6") (pintype "passive"))
      (node (ref "U3") (pin "j4") (pinfunction "INTVCC3_j4") (pintype "passive"))
    )
    (net (code "31") (name "Net-(U3-INTVCC4)") (class "Default")
      (node (ref "U3") (pin "k5") (pinfunction "INTVCC4_k5") (pintype "passive"))
      (node (ref "U3") (pin "l6") (pinfunction "MODE4_l6") (pintype "passive"))
    )
    (net (code "32") (name "Net-(U3-TEMP)") (class "Default")
      (node (ref "R7") (pin "2") (pinfunction "2_2") (pintype "passive"))
      (node (ref "U3") (pin "f3") (pinfunction "TEMP_f3") (pintype "passive"))
    )
    (net (code "33") (name "Net-(U3-TRACK{slash}SS1)") (class "Default")
      (node (ref "C10") (pin "2") (pinfunction "2_2") (pintype "passive"))
      (node (ref "U3") (pin "a6") (pinfunction "TRACK/SS1_a6") (pintype "passive"))
    )
    (net (code "34") (name "Net-(U3-TRACK{slash}SS2)") (class "Default")
      (node (ref "C12") (pin "2") (pinfunction "2_2") (pintype "passive"))
      (node (ref "U3") (pin "d6") (pinfunction "TRACK/SS2_d6") (pintype "passive"))
    )
    (net (code "35") (name "Net-(U3-TRACK{slash}SS3)") (class "Default")
      (node (ref "C14") (pin "2") (pinfunction "2_2") (pintype "passive"))
      (node (ref "U3") (pin "g6") (pinfunction "TRACK/SS3_g6") (pintype "passive"))
    )
    (net (code "36") (name "Net-(U3-TRACK{slash}SS4)") (class "Default")
      (node (ref "C16") (pin "2") (pinfunction "2_2") (pintype "passive"))
      (node (ref "U3") (pin "k6") (pinfunction "TRACK/SS4_k6") (pintype "passive"))
    )
    (net (code "37") (name "unconnected-(P2-Pad4)") (class "Default")
      (node (ref "P2") (pin "4") (pinfunction "4_4") (pintype "passive"))
    )
    (net (code "38") (name "unconnected-(P4A-CLK0_M2C_N-PadH5)") (class "Default")
      (node (ref "P4") (pin "H5") (pinfunction "CLK0_M2C_N_H5") (pintype "passive"))
    )
    (net (code "39") (name "unconnected-(P4A-CLK0_M2C_P-PadH4)") (class "Default")
      (node (ref "P4") (pin "H4") (pinfunction "CLK0_M2C_P_H4") (pintype "passive"))
    )
    (net (code "40") (name "unconnected-(P4A-LA02_N-PadH8)") (class "Default")
      (node (ref "P4") (pin "H8") (pinfunction "LA02_N_H8") (pintype "passive"))
    )
    (net (code "41") (name "unconnected-(P4A-LA02_P-PadH7)") (class "Default")
      (node (ref "P4") (pin "H7") (pinfunction "LA02_P_H7") (pintype "passive"))
    )
    (net (code "42") (name "unconnected-(P4A-LA04_N-PadH11)") (class "Default")
      (node (ref "P4") (pin "H11") (pinfunction "LA04_N_H11") (pintype "passive"))
    )
    (net (code "43") (name "unconnected-(P4A-LA04_P-PadH10)") (class "Default")
      (node (ref "P4") (pin "H10") (pinfunction "LA04_P_H10") (pintype "passive"))
    )
    (net (code "44") (name "unconnected-(P4A-LA07_N-PadH14)") (class "Default")
      (node (ref "P4") (pin "H14") (pinfunction "LA07_N_H14") (pintype "passive"))
    )
    (net (code "45") (name "unconnected-(P4A-LA07_P-PadH13)") (class "Default")
      (node (ref "P4") (pin "H13") (pinfunction "LA07_P_H13") (pintype "passive"))
    )
    (net (code "46") (name "unconnected-(P4A-LA11_N-PadH17)") (class "Default")
      (node (ref "P4") (pin "H17") (pinfunction "LA11_N_H17") (pintype "passive"))
    )
    (net (code "47") (name "unconnected-(P4A-LA11_P-PadH16)") (class "Default")
      (node (ref "P4") (pin "H16") (pinfunction "LA11_P_H16") (pintype "passive"))
    )
    (net (code "48") (name "unconnected-(P4A-LA15_N-PadH20)") (class "Default")
      (node (ref "P4") (pin "H20") (pinfunction "LA15_N_H20") (pintype "passive"))
    )
    (net (code "49") (name "unconnected-(P4A-LA15_P-PadH19)") (class "Default")
      (node (ref "P4") (pin "H19") (pinfunction "LA15_P_H19") (pintype "passive"))
    )
    (net (code "50") (name "unconnected-(P4A-LA19_N-PadH23)") (class "Default")
      (node (ref "P4") (pin "H23") (pinfunction "LA19_N_H23") (pintype "passive"))
    )
    (net (code "51") (name "unconnected-(P4A-LA19_P-PadH22)") (class "Default")
      (node (ref "P4") (pin "H22") (pinfunction "LA19_P_H22") (pintype "passive"))
    )
    (net (code "52") (name "unconnected-(P4A-LA21_P-PadH25)") (class "Default")
      (node (ref "P4") (pin "H25") (pinfunction "LA21_P_H25") (pintype "passive"))
    )
    (net (code "53") (name "unconnected-(P4A-LA32_N-PadH38)") (class "Default")
      (node (ref "P4") (pin "H38") (pinfunction "LA32_N_H38") (pintype "passive"))
    )
    (net (code "54") (name "unconnected-(P4A-PRSNT_M2C_L-PadH2)") (class "Default")
      (node (ref "P4") (pin "H2") (pinfunction "PRSNT_M2C_L_H2") (pintype "passive"))
    )
    (net (code "55") (name "unconnected-(P4A-VADJ-PadH40)") (class "Default")
      (node (ref "P4") (pin "H40") (pinfunction "VADJ_H40") (pintype "passive"))
    )
    (net (code "56") (name "unconnected-(P4A-VREF_A_M2C-PadH1)") (class "Default")
      (node (ref "P4") (pin "H1") (pinfunction "VREF_A_M2C_H1") (pintype "passive"))
    )
    (net (code "57") (name "unconnected-(P4B-CLK1_M2C_N-PadG3)") (class "Default")
      (node (ref "P4") (pin "G3") (pinfunction "CLK1_M2C_N_G3") (pintype "passive"))
    )
    (net (code "58") (name "unconnected-(P4B-CLK1_M2C_P-PadG2)") (class "Default")
      (node (ref "P4") (pin "G2") (pinfunction "CLK1_M2C_P_G2") (pintype "passive"))
    )
    (net (code "59") (name "unconnected-(P4B-LA00_N_CC-PadG7)") (class "Default")
      (node (ref "P4") (pin "G7") (pinfunction "LA00_N_CC_G7") (pintype "passive"))
    )
    (net (code "60") (name "unconnected-(P4B-LA00_P_CC-PadG6)") (class "Default")
      (node (ref "P4") (pin "G6") (pinfunction "LA00_P_CC_G6") (pintype "passive"))
    )
    (net (code "61") (name "unconnected-(P4B-LA03_N-PadG10)") (class "Default")
      (node (ref "P4") (pin "G10") (pinfunction "LA03_N_G10") (pintype "passive"))
    )
    (net (code "62") (name "unconnected-(P4B-LA03_P-PadG9)") (class "Default")
      (node (ref "P4") (pin "G9") (pinfunction "LA03_P_G9") (pintype "passive"))
    )
    (net (code "63") (name "unconnected-(P4B-LA08_N-PadG13)") (class "Default")
      (node (ref "P4") (pin "G13") (pinfunction "LA08_N_G13") (pintype "passive"))
    )
    (net (code "64") (name "unconnected-(P4B-LA08_P-PadG12)") (class "Default")
      (node (ref "P4") (pin "G12") (pinfunction "LA08_P_G12") (pintype "passive"))
    )
    (net (code "65") (name "unconnected-(P4B-LA12_N-PadG16)") (class "Default")
      (node (ref "P4") (pin "G16") (pinfunction "LA12_N_G16") (pintype "passive"))
    )
    (net (code "66") (name "unconnected-(P4B-LA12_P-PadG15)") (class "Default")
      (node (ref "P4") (pin "G15") (pinfunction "LA12_P_G15") (pintype "passive"))
    )
    (net (code "67") (name "unconnected-(P4B-LA16_N-PadG19)") (class "Default")
      (node (ref "P4") (pin "G19") (pinfunction "LA16_N_G19") (pintype "passive"))
    )
    (net (code "68") (name "unconnected-(P4B-LA16_P-PadG18)") (class "Default")
      (node (ref "P4") (pin "G18") (pinfunction "LA16_P_G18") (pintype "passive"))
    )
    (net (code "69") (name "unconnected-(P4B-LA20_N-PadG22)") (class "Default")
      (node (ref "P4") (pin "G22") (pinfunction "LA20_N_G22") (pintype "passive"))
    )
    (net (code "70") (name "unconnected-(P4B-LA20_P-PadG21)") (class "Default")
      (node (ref "P4") (pin "G21") (pinfunction "LA20_P_G21") (pintype "passive"))
    )
    (net (code "71") (name "unconnected-(P4B-LA22_N-PadG25)") (class "Default")
      (node (ref "P4") (pin "G25") (pinfunction "LA22_N_G25") (pintype "passive"))
    )
    (net (code "72") (name "unconnected-(P4B-LA22_P-PadG24)") (class "Default")
      (node (ref "P4") (pin "G24") (pinfunction "LA22_P_G24") (pintype "passive"))
    )
    (net (code "73") (name "unconnected-(P4B-LA25_N-PadG28)") (class "Default")
      (node (ref "P4") (pin "G28") (pinfunction "LA25_N_G28") (pintype "passive"))
    )
    (net (code "74") (name "unconnected-(P4B-LA25_P-PadG27)") (class "Default")
      (node (ref "P4") (pin "G27") (pinfunction "LA25_P_G27") (pintype "passive"))
    )
    (net (code "75") (name "unconnected-(P4B-LA29_N-PadG31)") (class "Default")
      (node (ref "P4") (pin "G31") (pinfunction "LA29_N_G31") (pintype "passive"))
    )
    (net (code "76") (name "unconnected-(P4B-LA29_P-PadG30)") (class "Default")
      (node (ref "P4") (pin "G30") (pinfunction "LA29_P_G30") (pintype "passive"))
    )
    (net (code "77") (name "unconnected-(P4B-LA31_N-PadG34)") (class "Default")
      (node (ref "P4") (pin "G34") (pinfunction "LA31_N_G34") (pintype "passive"))
    )
    (net (code "78") (name "unconnected-(P4B-LA31_P-PadG33)") (class "Default")
      (node (ref "P4") (pin "G33") (pinfunction "LA31_P_G33") (pintype "passive"))
    )
    (net (code "79") (name "unconnected-(P4B-LA33_N-PadG37)") (class "Default")
      (node (ref "P4") (pin "G37") (pinfunction "LA33_N_G37") (pintype "passive"))
    )
    (net (code "80") (name "unconnected-(P4B-LA33_P-PadG36)") (class "Default")
      (node (ref "P4") (pin "G36") (pinfunction "LA33_P_G36") (pintype "passive"))
    )
    (net (code "81") (name "unconnected-(P4B-VADJ-PadG39)") (class "Default")
      (node (ref "P4") (pin "G39") (pinfunction "VADJ_G39") (pintype "passive"))
    )
    (net (code "82") (name "unconnected-(P4C-3P3AUX-PadD32)") (class "Default")
      (node (ref "P4") (pin "D32") (pinfunction "3P3AUX_D32") (pintype "passive"))
    )
    (net (code "83") (name "unconnected-(P4C-GA1-PadD35)") (class "Default")
      (node (ref "P4") (pin "D35") (pinfunction "GA1_D35") (pintype "passive"))
    )
    (net (code "84") (name "unconnected-(P4C-GBTCLK0_M2C_N-PadD5)") (class "Default")
      (node (ref "P4") (pin "D5") (pinfunction "GBTCLK0_M2C_N_D5") (pintype "passive"))
    )
    (net (code "85") (name "unconnected-(P4C-GBTCLK0_M2C_P-PadD4)") (class "Default")
      (node (ref "P4") (pin "D4") (pinfunction "GBTCLK0_M2C_P_D4") (pintype "passive"))
    )
    (net (code "86") (name "unconnected-(P4C-LA01_N_CC-PadD9)") (class "Default")
      (node (ref "P4") (pin "D9") (pinfunction "LA01_N_CC_D9") (pintype "passive"))
    )
    (net (code "87") (name "unconnected-(P4C-LA01_P_CC-PadD8)") (class "Default")
      (node (ref "P4") (pin "D8") (pinfunction "LA01_P_CC_D8") (pintype "passive"))
    )
    (net (code "88") (name "unconnected-(P4C-LA05_N-PadD12)") (class "Default")
      (node (ref "P4") (pin "D12") (pinfunction "LA05_N_D12") (pintype "passive"))
    )
    (net (code "89") (name "unconnected-(P4C-LA05_P-PadD11)") (class "Default")
      (node (ref "P4") (pin "D11") (pinfunction "LA05_P_D11") (pintype "passive"))
    )
    (net (code "90") (name "unconnected-(P4C-LA09_N-PadD15)") (class "Default")
      (node (ref "P4") (pin "D15") (pinfunction "LA09_N_D15") (pintype "passive"))
    )
    (net (code "91") (name "unconnected-(P4C-LA09_P-PadD14)") (class "Default")
      (node (ref "P4") (pin "D14") (pinfunction "LA09_P_D14") (pintype "passive"))
    )
    (net (code "92") (name "unconnected-(P4C-LA13_N-PadD18)") (class "Default")
      (node (ref "P4") (pin "D18") (pinfunction "LA13_N_D18") (pintype "passive"))
    )
    (net (code "93") (name "unconnected-(P4C-LA13_P-PadD17)") (class "Default")
      (node (ref "P4") (pin "D17") (pinfunction "LA13_P_D17") (pintype "passive"))
    )
    (net (code "94") (name "unconnected-(P4C-LA17_N_CC-PadD21)") (class "Default")
      (node (ref "P4") (pin "D21") (pinfunction "LA17_N_CC_D21") (pintype "passive"))
    )
    (net (code "95") (name "unconnected-(P4C-LA17_P_CC-PadD20)") (class "Default")
      (node (ref "P4") (pin "D20") (pinfunction "LA17_P_CC_D20") (pintype "passive"))
    )
    (net (code "96") (name "unconnected-(P4C-LA23_N-PadD24)") (class "Default")
      (node (ref "P4") (pin "D24") (pinfunction "LA23_N_D24") (pintype "passive"))
    )
    (net (code "97") (name "unconnected-(P4C-LA23_P-PadD23)") (class "Default")
      (node (ref "P4") (pin "D23") (pinfunction "LA23_P_D23") (pintype "passive"))
    )
    (net (code "98") (name "unconnected-(P4C-LA26_N-PadD27)") (class "Default")
      (node (ref "P4") (pin "D27") (pinfunction "LA26_N_D27") (pintype "passive"))
    )
    (net (code "99") (name "unconnected-(P4C-LA26_P-PadD26)") (class "Default")
      (node (ref "P4") (pin "D26") (pinfunction "LA26_P_D26") (pintype "passive"))
    )
    (net (code "100") (name "unconnected-(P4C-PG_C2M-PadD1)") (class "Default")
      (node (ref "P4") (pin "D1") (pinfunction "PG_C2M_D1") (pintype "passive"))
    )
    (net (code "101") (name "unconnected-(P4C-TCK-PadD29)") (class "Default")
      (node (ref "P4") (pin "D29") (pinfunction "TCK_D29") (pintype "passive"))
    )
    (net (code "102") (name "unconnected-(P4C-TDI-PadD30)") (class "Default")
      (node (ref "P4") (pin "D30") (pinfunction "TDI_D30") (pintype "passive"))
    )
    (net (code "103") (name "unconnected-(P4C-TDO-PadD31)") (class "Default")
      (node (ref "P4") (pin "D31") (pinfunction "TDO_D31") (pintype "passive"))
    )
    (net (code "104") (name "unconnected-(P4C-TMS-PadD33)") (class "Default")
      (node (ref "P4") (pin "D33") (pinfunction "TMS_D33") (pintype "passive"))
    )
    (net (code "105") (name "unconnected-(P4C-TRST_L-PadD34)") (class "Default")
      (node (ref "P4") (pin "D34") (pinfunction "TRST_L_D34") (pintype "passive"))
    )
    (net (code "106") (name "unconnected-(P4D-DP0_C2M_N-PadC3)") (class "Default")
      (node (ref "P4") (pin "C3") (pinfunction "DP0_C2M_N_C3") (pintype "passive"))
    )
    (net (code "107") (name "unconnected-(P4D-DP0_C2M_P-PadC2)") (class "Default")
      (node (ref "P4") (pin "C2") (pinfunction "DP0_C2M_P_C2") (pintype "passive"))
    )
    (net (code "108") (name "unconnected-(P4D-DP0_M2C_N-PadC7)") (class "Default")
      (node (ref "P4") (pin "C7") (pinfunction "DP0_M2C_N_C7") (pintype "passive"))
    )
    (net (code "109") (name "unconnected-(P4D-DP0_M2C_P-PadC6)") (class "Default")
      (node (ref "P4") (pin "C6") (pinfunction "DP0_M2C_P_C6") (pintype "passive"))
    )
    (net (code "110") (name "unconnected-(P4D-GA0-PadC34)") (class "Default")
      (node (ref "P4") (pin "C34") (pinfunction "GA0_C34") (pintype "passive"))
    )
    (net (code "111") (name "unconnected-(P4D-LA06_N-PadC11)") (class "Default")
      (node (ref "P4") (pin "C11") (pinfunction "LA06_N_C11") (pintype "passive"))
    )
    (net (code "112") (name "unconnected-(P4D-LA06_P-PadC10)") (class "Default")
      (node (ref "P4") (pin "C10") (pinfunction "LA06_P_C10") (pintype "passive"))
    )
    (net (code "113") (name "unconnected-(P4D-LA10_N-PadC15)") (class "Default")
      (node (ref "P4") (pin "C15") (pinfunction "LA10_N_C15") (pintype "passive"))
    )
    (net (code "114") (name "unconnected-(P4D-LA10_P-PadC14)") (class "Default")
      (node (ref "P4") (pin "C14") (pinfunction "LA10_P_C14") (pintype "passive"))
    )
    (net (code "115") (name "unconnected-(P4D-LA14_N-PadC19)") (class "Default")
      (node (ref "P4") (pin "C19") (pinfunction "LA14_N_C19") (pintype "passive"))
    )
    (net (code "116") (name "unconnected-(P4D-LA14_P-PadC18)") (class "Default")
      (node (ref "P4") (pin "C18") (pinfunction "LA14_P_C18") (pintype "passive"))
    )
    (net (code "117") (name "unconnected-(P4D-LA18_N_CC-PadC23)") (class "Default")
      (node (ref "P4") (pin "C23") (pinfunction "LA18_N_CC_C23") (pintype "passive"))
    )
    (net (code "118") (name "unconnected-(P4D-LA18_P_CC-PadC22)") (class "Default")
      (node (ref "P4") (pin "C22") (pinfunction "LA18_P_CC_C22") (pintype "passive"))
    )
    (net (code "119") (name "unconnected-(P4D-LA27_N-PadC27)") (class "Default")
      (node (ref "P4") (pin "C27") (pinfunction "LA27_N_C27") (pintype "passive"))
    )
    (net (code "120") (name "unconnected-(P4D-LA27_P-PadC26)") (class "Default")
      (node (ref "P4") (pin "C26") (pinfunction "LA27_P_C26") (pintype "passive"))
    )
    (net (code "121") (name "unconnected-(P4D-SCL-PadC30)") (class "Default")
      (node (ref "P4") (pin "C30") (pinfunction "SCL_C30") (pintype "passive"))
    )
    (net (code "122") (name "unconnected-(P4D-SDA-PadC31)") (class "Default")
      (node (ref "P4") (pin "C31") (pinfunction "SDA_C31") (pintype "passive"))
    )
    (net (code "123") (name "unconnected-(U3-CLKIN-Padc7)") (class "Default")
      (node (ref "U3") (pin "c7") (pinfunction "CLKIN_c7") (pintype "passive"))
    )
    (net (code "124") (name "unconnected-(U3-CLKOUT-Padj3)") (class "Default")
      (node (ref "U3") (pin "j3") (pinfunction "CLKOUT_j3") (pintype "passive"))
    )
    (net (code "125") (name "unconnected-(U3-COMP1-Padb7)") (class "Default")
      (node (ref "U3") (pin "b7") (pinfunction "COMP1_b7") (pintype "passive"))
    )
    (net (code "126") (name "unconnected-(U3-COMP2-Pade7)") (class "Default")
      (node (ref "U3") (pin "e7") (pinfunction "COMP2_e7") (pintype "passive"))
    )
    (net (code "127") (name "unconnected-(U3-COMP3-Padh7)") (class "Default")
      (node (ref "U3") (pin "h7") (pinfunction "COMP3_h7") (pintype "passive"))
    )
    (net (code "128") (name "unconnected-(U3-COMP4-Padl7)") (class "Default")
      (node (ref "U3") (pin "l7") (pinfunction "COMP4_l7") (pintype "passive"))
    )
    (net (code "129") (name "unconnected-(U3-PGOOD1-Padc3)") (class "Default")
      (node (ref "U3") (pin "c3") (pinfunction "PGOOD1_c3") (pintype "passive"))
    )
    (net (code "130") (name "unconnected-(U3-PGOOD2-Padc2)") (class "Default")
      (node (ref "U3") (pin "c2") (pinfunction "PGOOD2_c2") (pintype "passive"))
    )
    (net (code "131") (name "unconnected-(U3-PGOOD3-Padf2)") (class "Default")
      (node (ref "U3") (pin "f2") (pinfunction "PGOOD3_f2") (pintype "passive"))
    )
    (net (code "132") (name "unconnected-(U3-PGOOD4-Padj2)") (class "Default")
      (node (ref "U3") (pin "j2") (pinfunction "PGOOD4_j2") (pintype "passive"))
    )
  )
)
